# XC7A35TFTG256_bank14.net
KiCad netlist of a schematic drawn in Altium Designer
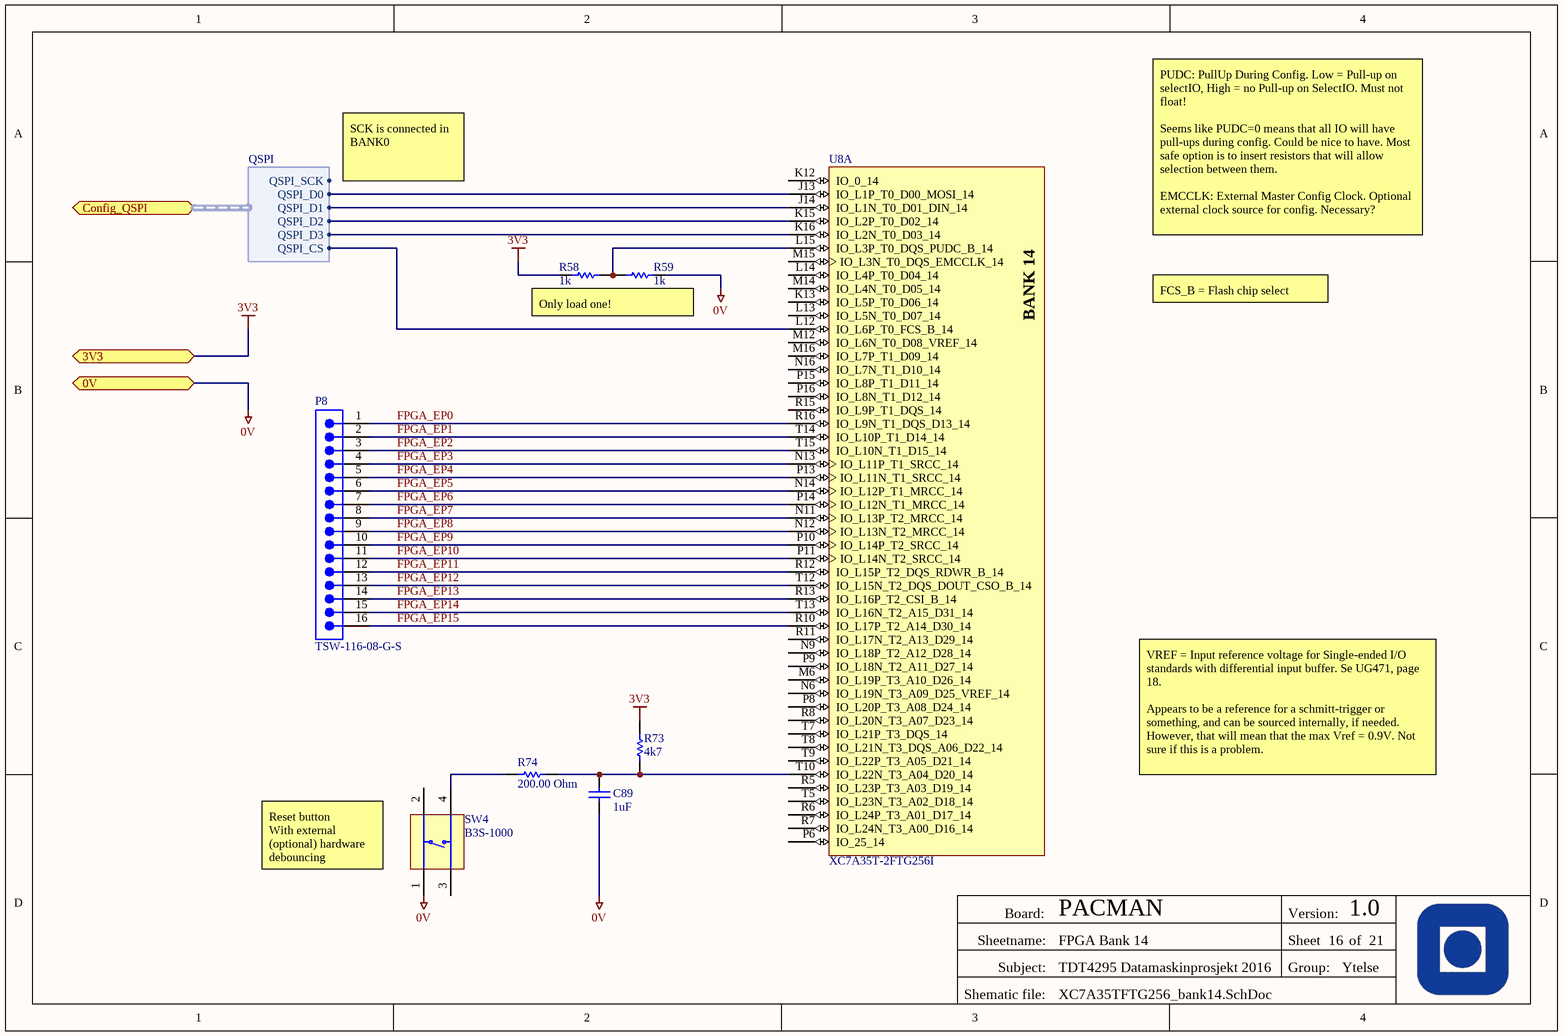
[diagram p0: XC7A35TFTG256_bank14.SchDoc]

(export (version "E")
  (design (tool "Eeschema 10.0.6"))
  (components
    (comp (ref "C89")
      (value "1uF")
      (footprint "CAPC0603(1608)100_N")
      (description "CAP 1uF 16V ±5% 0603 (1608 Metric) Thickness 1mm SMD")
      (fields (field (name "TOLERANCE") "Â±5%") (field (name "Comment") "CAP 1uF 16V 0603(1608)"))
      (libsource (lib "Altium Content Vault") (part "CMP-1035-02736-1"))
    )
    (comp (ref "P8")
      (value "TSW-116-08-G-S")
      (footprint "SMTC-TSW-116-08-X-S")
      (description "0.025\" SQ Post Header, Through-hole, Vertical, -55 to 125 degC, 2.54 mm Pitch, 16-Pin, Male, RoHS")
      (fields (field (name "MANUFACTURER") "Samtec"))
      (libsource (lib "Altium Content Vault") (part "SMTC-TSW-116-08-X-S"))
    )
    (comp (ref "R58")
      (value "1k")
      (footprint "RESC0603(1608)_L")
      (description "1K 0.1W 5% 0603 (1608 Metric)  SMD")
      (fields (field (name "TOLERANCE") "5 %") (field (name "POWER") "0.1 W"))
      (libsource (lib "Altium Content Vault") (part "CMP-1012-00074-1"))
    )
    (comp (ref "R59")
      (value "1k")
      (footprint "RESC0603(1608)_L")
      (description "1K 0.1W 5% 0603 (1608 Metric)  SMD")
      (fields (field (name "TOLERANCE") "5 %") (field (name "POWER") "0.1 W"))
      (libsource (lib "Altium Content Vault") (part "CMP-1012-00074-1"))
    )
    (comp (ref "R73")
      (value "4k7")
      (footprint "RESC0603(1608)_N")
      (description "4K7 0.1W 1% 0603 (1608 Metric)  SMD")
      (fields (field (name "POWER") "0.1 W") (field (name "TOLERANCE") "1 %"))
      (libsource (lib "Altium Content Vault") (part "CMP-1012-00586-1"))
    )
    (comp (ref "R74")
      (value "200.00 Ohm")
      (footprint "RESC0603(1608)_L")
      (description "200R 0.1W 5% 0603 (1608 Metric)  SMD")
      (fields (field (name "TOLERANCE") "5 %") (field (name "POWER") "0.1 W"))
      (libsource (lib "Altium Content Vault") (part "CMP-1012-00057-1"))
    )
    (comp (ref "SW4")
      (value "B3S-1000")
      (footprint "OMRON-B3S-1000-4_V")
      (description "Sealed Tactile Switch, SPST-NO, 3 to 24 V, -25 to 70 degC, 4-Pin SMD, RoHS, Bulk")
      (libsource (lib "Altium Content Vault") (part "SW-SPST-4_A"))
    )
    (comp (ref "U8")
      (value "XC7A35T-2FTG256I")
      (footprint "FTG256")
      (description "Artix-7 FPGA, 170 User I/Os, 0 GTP, 256-Ball BGA, Speed Grade 2, Industrial Grade, Pb-Free")
      (fields (field (name "MANUFACTURER") "Xilinx"))
      (libsource (lib "Altium Content Vault") (part "XLNX-XC7A35T-FTG256"))
    )
  )
  (nets
    (net (code "2") (name "/FPGA_EP0") (class "Default")
      (node (ref "P8") (pin "1") (pinfunction "1_1") (pintype "passive"))
      (node (ref "U8") (pin "R16") (pinfunction "IO_L9N_T1_DQS_D13_14_R16") (pintype "bidirectional"))
    )
    (net (code "3") (name "/FPGA_EP1") (class "Default")
      (node (ref "P8") (pin "2") (pinfunction "2_2") (pintype "passive"))
      (node (ref "U8") (pin "T14") (pinfunction "IO_L10P_T1_D14_14_T14") (pintype "bidirectional"))
    )
    (net (code "4") (name "/FPGA_EP2") (class "Default")
      (node (ref "P8") (pin "3") (pinfunction "3_3") (pintype "passive"))
      (node (ref "U8") (pin "T15") (pinfunction "IO_L10N_T1_D15_14_T15") (pintype "bidirectional"))
    )
    (net (code "5") (name "/FPGA_EP3") (class "Default")
      (node (ref "P8") (pin "4") (pinfunction "4_4") (pintype "passive"))
      (node (ref "U8") (pin "N13") (pinfunction "IO_L11P_T1_SRCC_14_N13") (pintype "bidirectional"))
    )
    (net (code "6") (name "/FPGA_EP4") (class "Default")
      (node (ref "P8") (pin "5") (pinfunction "5_5") (pintype "passive"))
      (node (ref "U8") (pin "P13") (pinfunction "IO_L11N_T1_SRCC_14_P13") (pintype "bidirectional"))
    )
    (net (code "7") (name "/FPGA_EP5") (class "Default")
      (node (ref "P8") (pin "6") (pinfunction "6_6") (pintype "passive"))
      (node (ref "U8") (pin "N14") (pinfunction "IO_L12P_T1_MRCC_14_N14") (pintype "bidirectional"))
    )
    (net (code "8") (name "/FPGA_EP6") (class "Default")
      (node (ref "P8") (pin "7") (pinfunction "7_7") (pintype "passive"))
      (node (ref "U8") (pin "P14") (pinfunction "IO_L12N_T1_MRCC_14_P14") (pintype "bidirectional"))
    )
    (net (code "9") (name "/FPGA_EP7") (class "Default")
      (node (ref "P8") (pin "8") (pinfunction "8_8") (pintype "passive"))
      (node (ref "U8") (pin "N11") (pinfunction "IO_L13P_T2_MRCC_14_N11") (pintype "bidirectional"))
    )
    (net (code "10") (name "/FPGA_EP8") (class "Default")
      (node (ref "P8") (pin "9") (pinfunction "9_9") (pintype "passive"))
      (node (ref "U8") (pin "N12") (pinfunction "IO_L13N_T2_MRCC_14_N12") (pintype "bidirectional"))
    )
    (net (code "11") (name "/FPGA_EP9") (class "Default")
      (node (ref "P8") (pin "10") (pinfunction "10_10") (pintype "passive"))
      (node (ref "U8") (pin "P10") (pinfunction "IO_L14P_T2_SRCC_14_P10") (pintype "bidirectional"))
    )
    (net (code "12") (name "/FPGA_EP10") (class "Default")
      (node (ref "P8") (pin "11") (pinfunction "11_11") (pintype "passive"))
      (node (ref "U8") (pin "P11") (pinfunction "IO_L14N_T2_SRCC_14_P11") (pintype "bidirectional"))
    )
    (net (code "13") (name "/FPGA_EP11") (class "Default")
      (node (ref "P8") (pin "12") (pinfunction "12_12") (pintype "passive"))
      (node (ref "U8") (pin "R12") (pinfunction "IO_L15P_T2_DQS_RDWR_B_14_R12") (pintype "bidirectional"))
    )
    (net (code "14") (name "/FPGA_EP12") (class "Default")
      (node (ref "P8") (pin "13") (pinfunction "13_13") (pintype "passive"))
      (node (ref "U8") (pin "T12") (pinfunction "IO_L15N_T2_DQS_DOUT_CSO_B_14_T12") (pintype "bidirectional"))
    )
    (net (code "15") (name "/FPGA_EP13") (class "Default")
      (node (ref "P8") (pin "14") (pinfunction "14_14") (pintype "passive"))
      (node (ref "U8") (pin "R13") (pinfunction "IO_L16P_T2_CSI_B_14_R13") (pintype "bidirectional"))
    )
    (net (code "16") (name "/FPGA_EP14") (class "Default")
      (node (ref "P8") (pin "15") (pinfunction "15_15") (pintype "passive"))
      (node (ref "U8") (pin "T13") (pinfunction "IO_L16N_T2_A15_D31_14_T13") (pintype "bidirectional"))
    )
    (net (code "17") (name "/FPGA_EP15") (class "Default")
      (node (ref "P8") (pin "16") (pinfunction "16_16") (pintype "passive"))
      (node (ref "U8") (pin "R10") (pinfunction "IO_L17P_T2_A14_D30_14_R10") (pintype "bidirectional"))
    )
    (net (code "18") (name "/QSPI_CS") (class "Default")
      (node (ref "U8") (pin "L12") (pinfunction "IO_L6P_T0_FCS_B_14_L12") (pintype "bidirectional"))
    )
    (net (code "19") (name "/QSPI_D0") (class "Default")
      (node (ref "U8") (pin "J13") (pinfunction "IO_L1P_T0_D00_MOSI_14_J13") (pintype "bidirectional"))
    )
    (net (code "20") (name "/QSPI_D1") (class "Default")
      (node (ref "U8") (pin "J14") (pinfunction "IO_L1N_T0_D01_DIN_14_J14") (pintype "bidirectional"))
    )
    (net (code "21") (name "/QSPI_D2") (class "Default")
      (node (ref "U8") (pin "K15") (pinfunction "IO_L2P_T0_D02_14_K15") (pintype "bidirectional"))
    )
    (net (code "22") (name "/QSPI_D3") (class "Default")
      (node (ref "U8") (pin "K16") (pinfunction "IO_L2N_T0_D03_14_K16") (pintype "bidirectional"))
    )
    (net (code "24") (name "0V") (class "Default")
      (node (ref "C89") (pin "1") (pinfunction "1_1") (pintype "passive"))
      (node (ref "R59") (pin "2") (pinfunction "2_2") (pintype "passive"))
      (node (ref "SW4") (pin "1") (pinfunction "1_1") (pintype "passive"))
    )
    (net (code "25") (name "3V3") (class "Default")
      (node (ref "R58") (pin "1") (pinfunction "1_1") (pintype "passive"))
      (node (ref "R73") (pin "2") (pinfunction "2_2") (pintype "passive"))
    )
    (net (code "26") (name "Net-(R74-Pad1)") (class "Default")
      (node (ref "R74") (pin "1") (pinfunction "1_1") (pintype "passive"))
      (node (ref "SW4") (pin "4") (pinfunction "4_4") (pintype "passive"))
    )
    (net (code "27") (name "Net-(U8A-IO_L3P_T0_DQS_PUDC_B_14)") (class "Default")
      (node (ref "R58") (pin "2") (pinfunction "2_2") (pintype "passive"))
      (node (ref "R59") (pin "1") (pinfunction "1_1") (pintype "passive"))
      (node (ref "U8") (pin "L15") (pinfunction "IO_L3P_T0_DQS_PUDC_B_14_L15") (pintype "bidirectional"))
    )
    (net (code "28") (name "Net-(U8A-IO_L22N_T3_A04_D20_14)") (class "Default")
      (node (ref "C89") (pin "2") (pinfunction "2_2") (pintype "passive"))
      (node (ref "R73") (pin "1") (pinfunction "1_1") (pintype "passive"))
      (node (ref "R74") (pin "2") (pinfunction "2_2") (pintype "passive"))
      (node (ref "U8") (pin "T10") (pinfunction "IO_L22N_T3_A04_D20_14_T10") (pintype "bidirectional"))
    )
    (net (code "29") (name "unconnected-(SW4-Pad2)") (class "Default")
      (node (ref "SW4") (pin "2") (pinfunction "2_2") (pintype "passive"))
    )
    (net (code "30") (name "unconnected-(SW4-Pad3)") (class "Default")
      (node (ref "SW4") (pin "3") (pinfunction "3_3") (pintype "passive"))
    )
    (net (code "31") (name "unconnected-(U8A-IO_0_14-PadK12)") (class "Default")
      (node (ref "U8") (pin "K12") (pinfunction "IO_0_14_K12") (pintype "bidirectional"))
    )
    (net (code "32") (name "unconnected-(U8A-IO_25_14-PadP6)") (class "Default")
      (node (ref "U8") (pin "P6") (pinfunction "IO_25_14_P6") (pintype "bidirectional"))
    )
    (net (code "33") (name "unconnected-(U8A-IO_L3N_T0_DQS_EMCCLK_14-PadM15)") (class "Default")
      (node (ref "U8") (pin "M15") (pinfunction "IO_L3N_T0_DQS_EMCCLK_14_M15") (pintype "bidirectional"))
    )
    (net (code "34") (name "unconnected-(U8A-IO_L4N_T0_D05_14-PadM14)") (class "Default")
      (node (ref "U8") (pin "M14") (pinfunction "IO_L4N_T0_D05_14_M14") (pintype "bidirectional"))
    )
    (net (code "35") (name "unconnected-(U8A-IO_L4P_T0_D04_14-PadL14)") (class "Default")
      (node (ref "U8") (pin "L14") (pinfunction "IO_L4P_T0_D04_14_L14") (pintype "bidirectional"))
    )
    (net (code "36") (name "unconnected-(U8A-IO_L5N_T0_D07_14-PadL13)") (class "Default")
      (node (ref "U8") (pin "L13") (pinfunction "IO_L5N_T0_D07_14_L13") (pintype "bidirectional"))
    )
    (net (code "37") (name "unconnected-(U8A-IO_L5P_T0_D06_14-PadK13)") (class "Default")
      (node (ref "U8") (pin "K13") (pinfunction "IO_L5P_T0_D06_14_K13") (pintype "bidirectional"))
    )
    (net (code "38") (name "unconnected-(U8A-IO_L6N_T0_D08_VREF_14-PadM12)") (class "Default")
      (node (ref "U8") (pin "M12") (pinfunction "IO_L6N_T0_D08_VREF_14_M12") (pintype "bidirectional"))
    )
    (net (code "39") (name "unconnected-(U8A-IO_L7N_T1_D10_14-PadN16)") (class "Default")
      (node (ref "U8") (pin "N16") (pinfunction "IO_L7N_T1_D10_14_N16") (pintype "bidirectional"))
    )
    (net (code "40") (name "unconnected-(U8A-IO_L7P_T1_D09_14-PadM16)") (class "Default")
      (node (ref "U8") (pin "M16") (pinfunction "IO_L7P_T1_D09_14_M16") (pintype "bidirectional"))
    )
    (net (code "41") (name "unconnected-(U8A-IO_L8N_T1_D12_14-PadP16)") (class "Default")
      (node (ref "U8") (pin "P16") (pinfunction "IO_L8N_T1_D12_14_P16") (pintype "bidirectional"))
    )
    (net (code "42") (name "unconnected-(U8A-IO_L8P_T1_D11_14-PadP15)") (class "Default")
      (node (ref "U8") (pin "P15") (pinfunction "IO_L8P_T1_D11_14_P15") (pintype "bidirectional"))
    )
    (net (code "43") (name "unconnected-(U8A-IO_L9P_T1_DQS_14-PadR15)") (class "Default")
      (node (ref "U8") (pin "R15") (pinfunction "IO_L9P_T1_DQS_14_R15") (pintype "bidirectional"))
    )
    (net (code "44") (name "unconnected-(U8A-IO_L17N_T2_A13_D29_14-PadR11)") (class "Default")
      (node (ref "U8") (pin "R11") (pinfunction "IO_L17N_T2_A13_D29_14_R11") (pintype "bidirectional"))
    )
    (net (code "45") (name "unconnected-(U8A-IO_L18N_T2_A11_D27_14-PadP9)") (class "Default")
      (node (ref "U8") (pin "P9") (pinfunction "IO_L18N_T2_A11_D27_14_P9") (pintype "bidirectional"))
    )
    (net (code "46") (name "unconnected-(U8A-IO_L18P_T2_A12_D28_14-PadN9)") (class "Default")
      (node (ref "U8") (pin "N9") (pinfunction "IO_L18P_T2_A12_D28_14_N9") (pintype "bidirectional"))
    )
    (net (code "47") (name "unconnected-(U8A-IO_L19N_T3_A09_D25_VREF_14-PadN6)") (class "Default")
      (node (ref "U8") (pin "N6") (pinfunction "IO_L19N_T3_A09_D25_VREF_14_N6") (pintype "bidirectional"))
    )
    (net (code "48") (name "unconnected-(U8A-IO_L19P_T3_A10_D26_14-PadM6)") (class "Default")
      (node (ref "U8") (pin "M6") (pinfunction "IO_L19P_T3_A10_D26_14_M6") (pintype "bidirectional"))
    )
    (net (code "49") (name "unconnected-(U8A-IO_L20N_T3_A07_D23_14-PadR8)") (class "Default")
      (node (ref "U8") (pin "R8") (pinfunction "IO_L20N_T3_A07_D23_14_R8") (pintype "bidirectional"))
    )
    (net (code "50") (name "unconnected-(U8A-IO_L20P_T3_A08_D24_14-PadP8)") (class "Default")
      (node (ref "U8") (pin "P8") (pinfunction "IO_L20P_T3_A08_D24_14_P8") (pintype "bidirectional"))
    )
    (net (code "51") (name "unconnected-(U8A-IO_L21N_T3_DQS_A06_D22_14-PadT8)") (class "Default")
      (node (ref "U8") (pin "T8") (pinfunction "IO_L21N_T3_DQS_A06_D22_14_T8") (pintype "bidirectional"))
    )
    (net (code "52") (name "unconnected-(U8A-IO_L21P_T3_DQS_14-PadT7)") (class "Default")
      (node (ref "U8") (pin "T7") (pinfunction "IO_L21P_T3_DQS_14_T7") (pintype "bidirectional"))
    )
    (net (code "53") (name "unconnected-(U8A-IO_L22P_T3_A05_D21_14-PadT9)") (class "Default")
      (node (ref "U8") (pin "T9") (pinfunction "IO_L22P_T3_A05_D21_14_T9") (pintype "bidirectional"))
    )
    (net (code "54") (name "unconnected-(U8A-IO_L23N_T3_A02_D18_14-PadT5)") (class "Default")
      (node (ref "U8") (pin "T5") (pinfunction "IO_L23N_T3_A02_D18_14_T5") (pintype "bidirectional"))
    )
    (net (code "55") (name "unconnected-(U8A-IO_L23P_T3_A03_D19_14-PadR5)") (class "Default")
      (node (ref "U8") (pin "R5") (pinfunction "IO_L23P_T3_A03_D19_14_R5") (pintype "bidirectional"))
    )
    (net (code "56") (name "unconnected-(U8A-IO_L24N_T3_A00_D16_14-PadR7)") (class "Default")
      (node (ref "U8") (pin "R7") (pinfunction "IO_L24N_T3_A00_D16_14_R7") (pintype "bidirectional"))
    )
    (net (code "57") (name "unconnected-(U8A-IO_L24P_T3_A01_D17_14-PadR6)") (class "Default")
      (node (ref "U8") (pin "R6") (pinfunction "IO_L24P_T3_A01_D17_14_R6") (pintype "bidirectional"))
    )
  )
)
